# 04_MCU.net
KiCad netlist of a schematic drawn in Altium Designer
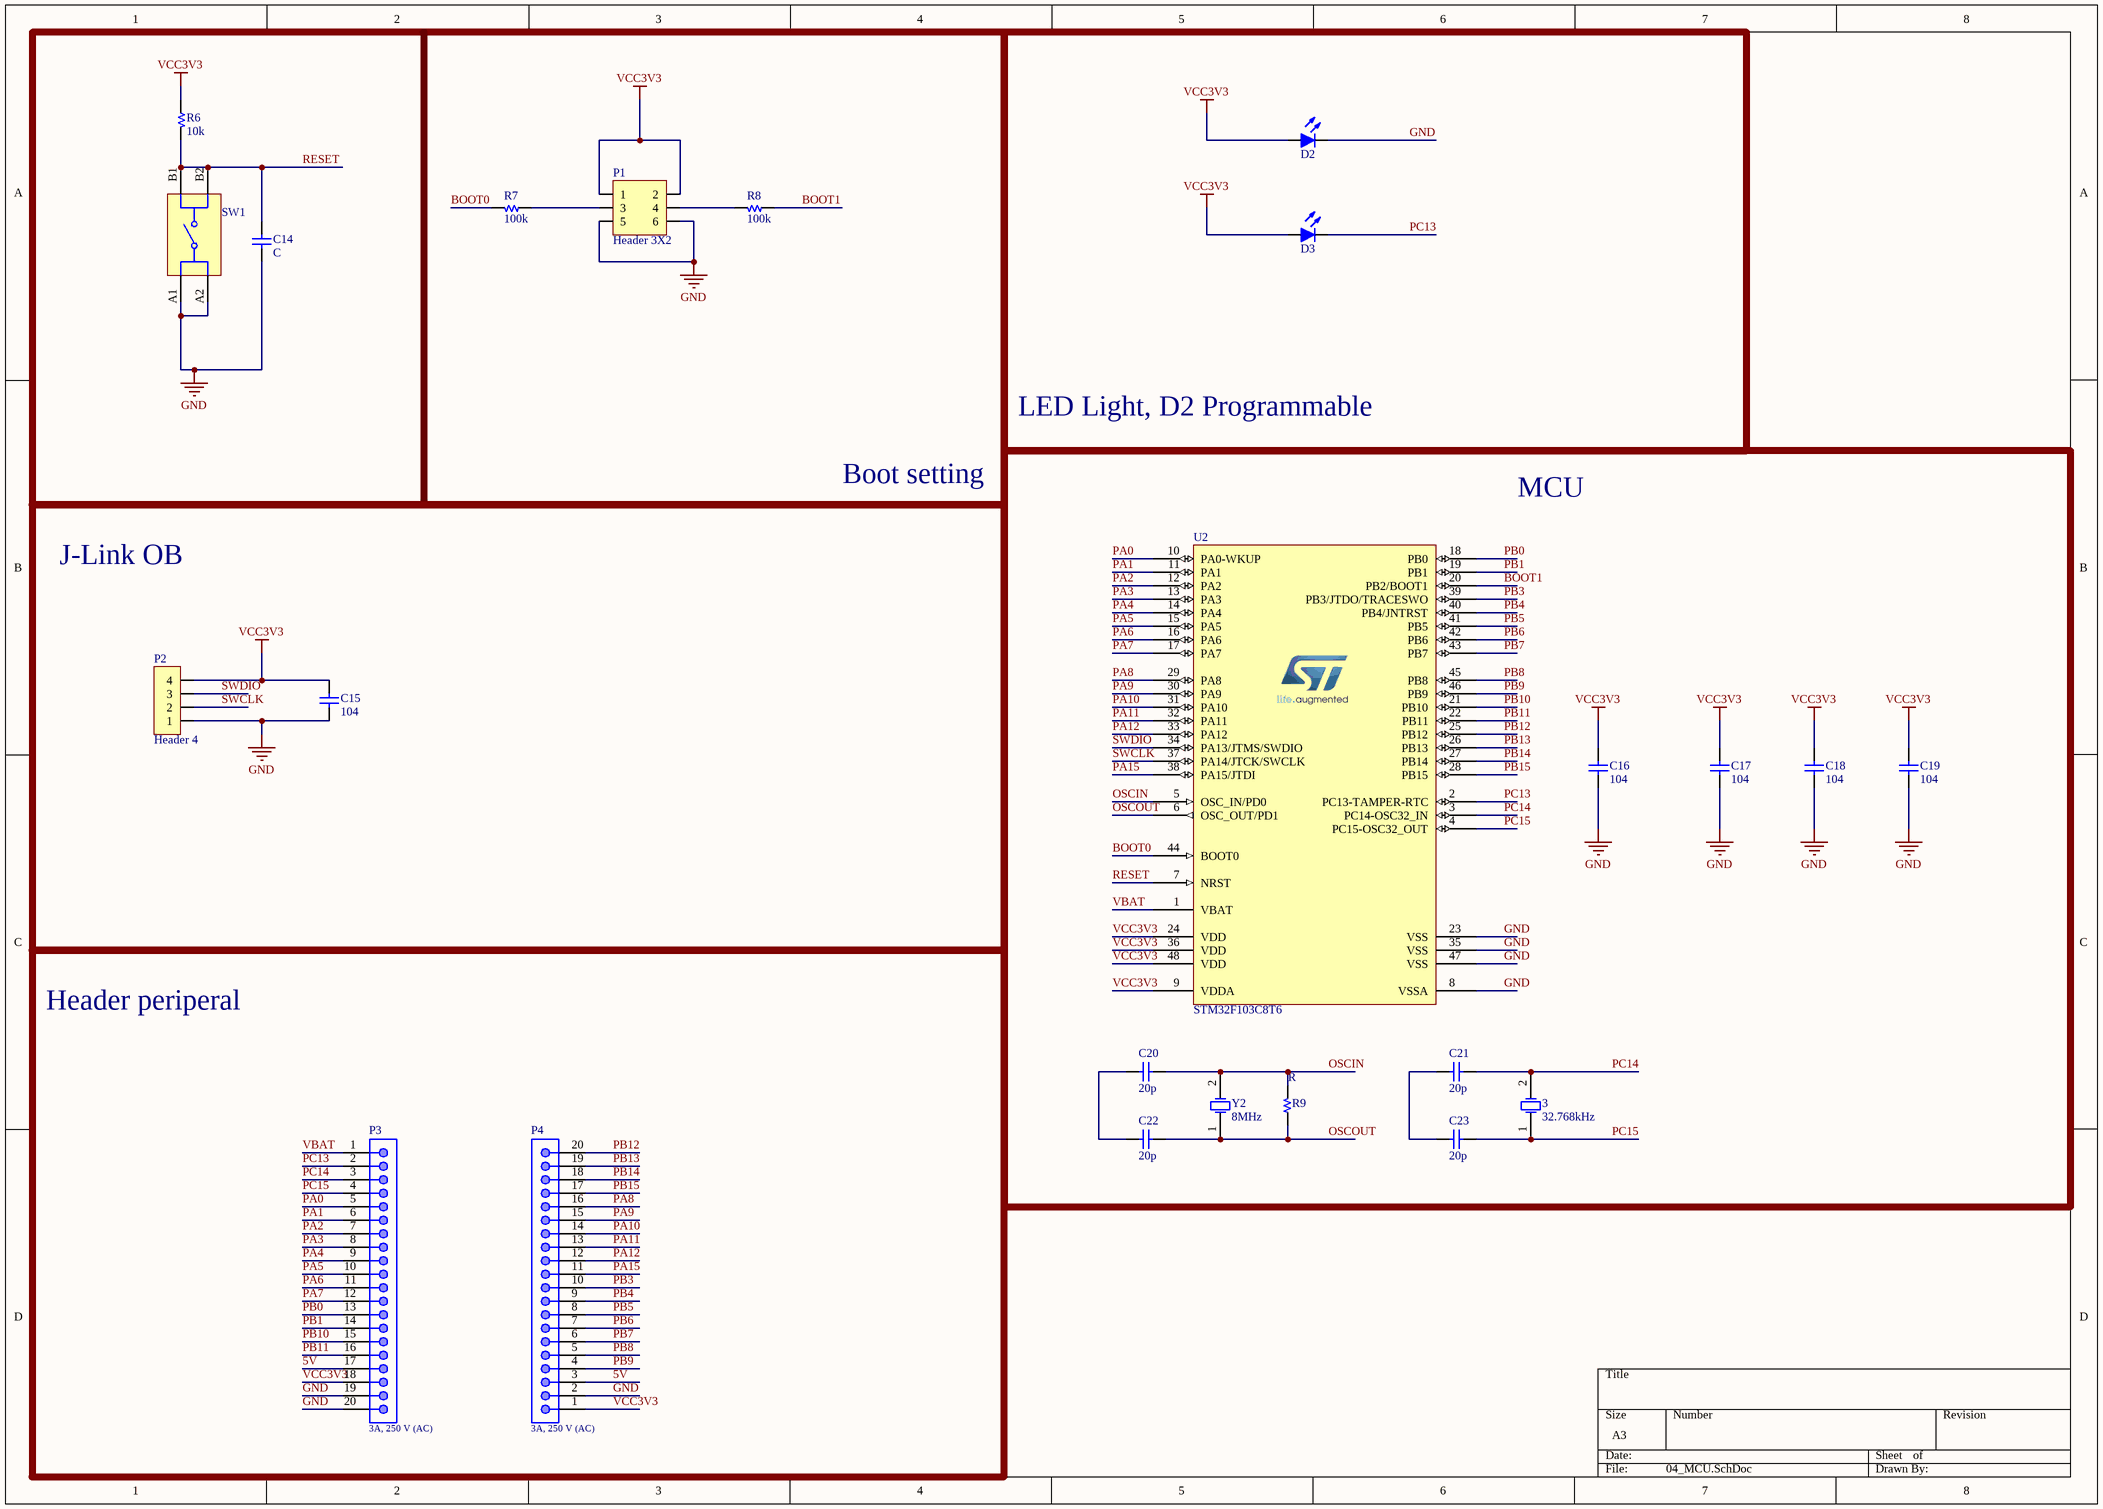
[diagram p0: 04_MCU.SchDoc]

(export (version "E")
  (design (tool "Eeschema 10.0.6"))
  (components
    (comp (ref "3")
      (value "32.768kHz")
      (footprint "XKXGI-SUA-32.768K")
      (description "32.768kHz Surface Mount Crystal 12.5pF ±20ppm ±30ppm SMD3215-2P Crystals ROHS")
      (fields (field (name "LCSC PART #") "C5213671") (field (name "MANUFACTURER") "YXC Crystal Oscillators"))
      (libsource (lib "Altium_XTAL_WATCH") (part "XKXGI-SUA-32.768K"))
    )
    (comp (ref "C14")
      (value "C")
      (footprint "C 0603")
      (description "Capacitor non-pol")
      (libsource (lib "chipfc_libs") (part "Capacitor NP"))
    )
    (comp (ref "C15")
      (value "104")
      (footprint "C 0805")
      (description "Capacitor non-pol")
      (libsource (lib "chipfc_libs") (part "Capacitor NP"))
    )
    (comp (ref "C16")
      (value "104")
      (footprint "C 0805")
      (description "Capacitor non-pol")
      (libsource (lib "chipfc_libs") (part "Capacitor NP"))
    )
    (comp (ref "C17")
      (value "104")
      (footprint "C 0805")
      (description "Capacitor non-pol")
      (libsource (lib "chipfc_libs") (part "Capacitor NP"))
    )
    (comp (ref "C18")
      (value "104")
      (footprint "C 0805")
      (description "Capacitor non-pol")
      (libsource (lib "chipfc_libs") (part "Capacitor NP"))
    )
    (comp (ref "C19")
      (value "104")
      (footprint "C 0805")
      (description "Capacitor non-pol")
      (libsource (lib "chipfc_libs") (part "Capacitor NP"))
    )
    (comp (ref "C20")
      (value "20p")
      (footprint "C 0805")
      (description "Capacitor non-pol")
      (libsource (lib "chipfc_libs") (part "Capacitor NP"))
    )
    (comp (ref "C21")
      (value "20p")
      (footprint "C 0805")
      (description "Capacitor non-pol")
      (libsource (lib "chipfc_libs") (part "Capacitor NP"))
    )
    (comp (ref "C22")
      (value "20p")
      (footprint "C 0805")
      (description "Capacitor non-pol")
      (libsource (lib "chipfc_libs") (part "Capacitor NP"))
    )
    (comp (ref "C23")
      (value "20p")
      (footprint "C 0805")
      (description "Capacitor non-pol")
      (libsource (lib "chipfc_libs") (part "Capacitor NP"))
    )
    (comp (ref "D2")
      (value "Led")
      (footprint "Led 0805")
      (description "Typical LED")
      (libsource (lib "led") (part "Led"))
    )
    (comp (ref "D3")
      (value "Led")
      (footprint "Led 0805")
      (description "Typical LED")
      (libsource (lib "led") (part "Led"))
    )
    (comp (ref "P1")
      (value "Header 3X2")
      (footprint "HDR/Header/6/DL")
      (description "Header, 3-Pin, Dual row")
      (libsource (lib "connectors") (part "Header 3X2"))
    )
    (comp (ref "P2")
      (value "Header 4")
      (footprint "HDR/Header/4")
      (description "Header, 4-Pin")
      (libsource (lib "connectors") (part "Header 4"))
    )
    (comp (ref "P3")
      (value "3A, 250 V (AC)")
      (footprint "61302011121")
      (description "WR-PHD Pin Header, THT, pitch 2.54mm, Single Row, Vertical, 20p")
      (fields
        (field (name "MANUFACTURER PART NUMBER") "61302011121")
        (field (name "MANUFACTURER") "Wurth Elektronik")
      )
      (libsource (lib "WR-PHD_Pin Header_2.54mm") (part "61302011121"))
    )
    (comp (ref "P4")
      (value "3A, 250 V (AC)")
      (footprint "61302011121")
      (description "WR-PHD Pin Header, THT, pitch 2.54mm, Single Row, Vertical, 20p")
      (fields
        (field (name "MANUFACTURER PART NUMBER") "61302011121")
        (field (name "MANUFACTURER") "Wurth Elektronik")
      )
      (libsource (lib "WR-PHD_Pin Header_2.54mm") (part "61302011121"))
    )
    (comp (ref "R6")
      (value "10k")
      (footprint "R 0805")
      (description "Resistor")
      (libsource (lib "chipfc_libs") (part "Resistor"))
    )
    (comp (ref "R7")
      (value "100k")
      (footprint "R 0805")
      (description "Resistor")
      (libsource (lib "chipfc_libs") (part "Resistor"))
    )
    (comp (ref "R8")
      (value "100k")
      (footprint "R 0805")
      (description "Resistor")
      (libsource (lib "chipfc_libs") (part "Resistor"))
    )
    (comp (ref "R9")
      (value "R")
      (footprint "R 0805")
      (description "Resistor")
      (libsource (lib "chipfc_libs") (part "Resistor"))
    )
    (comp (ref "SW1")
      (value "430152043826")
      (footprint "WS-TASV_L6W6H4.3_4301x20438x6")
      (description "WS-TASV SMT Tact Switch, L6 x W6 x H4.3mm, 260g, SPST-NO, 12V, 50mA")
      (fields (field (name "MANUFACTURER") "Wurth Elektronik"))
      (libsource (lib "Button") (part "430152043826"))
    )
    (comp (ref "U2")
      (value "STM32F103C8T6")
      (footprint "STM32F103C8T6")
      (description "ARM Microcontrollers - MCU 32BIT Cortex M3 64KB 20KB RAM 2X12 ADC")
      (fields
        (field (name "MANUFACTURER") "STMicroelectronics")
        (field (name "MANUFACTURER PART NUMBER") "STM32F103C8T6TR")
      )
      (libsource (lib "STM32") (part "STM32F103C8T6"))
    )
    (comp (ref "Y2")
      (value "8MHz")
      (footprint "WE-XTAL_HC49/4HSMX")
      (description "WE-XTAL Quartz Crystal, SMT, HC49/4HSMX, 8MHz, +/-30ppm")
      (fields
        (field (name "MANUFACTURER PART NUMBER") "830003151")
        (field (name "MANUFACTURER") "Wurth Elektronik")
      )
      (libsource (lib "Altium_XTAL_2PIN") (part "071105086016"))
    )
  )
  (nets
    (net (code "1") (name "/5V") (class "Default")
      (node (ref "P3") (pin "17") (pinfunction "17_17") (pintype "passive"))
      (node (ref "P4") (pin "3") (pinfunction "3_3") (pintype "passive"))
    )
    (net (code "2") (name "/BOOT0") (class "Default")
      (node (ref "R7") (pin "2") (pinfunction "2_2") (pintype "passive"))
      (node (ref "U2") (pin "44") (pinfunction "BOOT0_44") (pintype "input"))
    )
    (net (code "3") (name "/BOOT1") (class "Default")
      (node (ref "R8") (pin "1") (pinfunction "1_1") (pintype "passive"))
      (node (ref "U2") (pin "20") (pinfunction "PB2/BOOT1_20") (pintype "bidirectional"))
    )
    (net (code "4") (name "/OSCIN") (class "Default")
      (node (ref "C20") (pin "1") (pinfunction "1_1") (pintype "passive"))
      (node (ref "R9") (pin "2") (pinfunction "2_2") (pintype "passive"))
      (node (ref "U2") (pin "5") (pinfunction "OSC_IN/PD0_5") (pintype "input"))
      (node (ref "Y2") (pin "2") (pinfunction "OSC2_2") (pintype "passive"))
    )
    (net (code "5") (name "/OSCOUT") (class "Default")
      (node (ref "C22") (pin "1") (pinfunction "1_1") (pintype "passive"))
      (node (ref "R9") (pin "1") (pinfunction "1_1") (pintype "passive"))
      (node (ref "U2") (pin "6") (pinfunction "OSC_OUT/PD1_6") (pintype "output"))
      (node (ref "Y2") (pin "1") (pinfunction "OSC1_1") (pintype "passive"))
    )
    (net (code "6") (name "/PA0") (class "Default")
      (node (ref "P3") (pin "5") (pinfunction "5_5") (pintype "passive"))
      (node (ref "U2") (pin "10") (pinfunction "PA0-WKUP_10") (pintype "bidirectional"))
    )
    (net (code "7") (name "/PA1") (class "Default")
      (node (ref "P3") (pin "6") (pinfunction "6_6") (pintype "passive"))
      (node (ref "U2") (pin "11") (pinfunction "PA1_11") (pintype "bidirectional"))
    )
    (net (code "8") (name "/PA2") (class "Default")
      (node (ref "P3") (pin "7") (pinfunction "7_7") (pintype "passive"))
      (node (ref "U2") (pin "12") (pinfunction "PA2_12") (pintype "bidirectional"))
    )
    (net (code "9") (name "/PA3") (class "Default")
      (node (ref "P3") (pin "8") (pinfunction "8_8") (pintype "passive"))
      (node (ref "U2") (pin "13") (pinfunction "PA3_13") (pintype "bidirectional"))
    )
    (net (code "10") (name "/PA4") (class "Default")
      (node (ref "P3") (pin "9") (pinfunction "9_9") (pintype "passive"))
      (node (ref "U2") (pin "14") (pinfunction "PA4_14") (pintype "bidirectional"))
    )
    (net (code "11") (name "/PA5") (class "Default")
      (node (ref "P3") (pin "10") (pinfunction "10_10") (pintype "passive"))
      (node (ref "U2") (pin "15") (pinfunction "PA5_15") (pintype "bidirectional"))
    )
    (net (code "12") (name "/PA6") (class "Default")
      (node (ref "P3") (pin "11") (pinfunction "11_11") (pintype "passive"))
      (node (ref "U2") (pin "16") (pinfunction "PA6_16") (pintype "bidirectional"))
    )
    (net (code "13") (name "/PA7") (class "Default")
      (node (ref "P3") (pin "12") (pinfunction "12_12") (pintype "passive"))
      (node (ref "U2") (pin "17") (pinfunction "PA7_17") (pintype "bidirectional"))
    )
    (net (code "14") (name "/PA8") (class "Default")
      (node (ref "P4") (pin "16") (pinfunction "16_16") (pintype "passive"))
      (node (ref "U2") (pin "29") (pinfunction "PA8_29") (pintype "bidirectional"))
    )
    (net (code "15") (name "/PA9") (class "Default")
      (node (ref "P4") (pin "15") (pinfunction "15_15") (pintype "passive"))
      (node (ref "U2") (pin "30") (pinfunction "PA9_30") (pintype "bidirectional"))
    )
    (net (code "16") (name "/PA10") (class "Default")
      (node (ref "P4") (pin "14") (pinfunction "14_14") (pintype "passive"))
      (node (ref "U2") (pin "31") (pinfunction "PA10_31") (pintype "bidirectional"))
    )
    (net (code "17") (name "/PA11") (class "Default")
      (node (ref "P4") (pin "13") (pinfunction "13_13") (pintype "passive"))
      (node (ref "U2") (pin "32") (pinfunction "PA11_32") (pintype "bidirectional"))
    )
    (net (code "18") (name "/PA12") (class "Default")
      (node (ref "P4") (pin "12") (pinfunction "12_12") (pintype "passive"))
      (node (ref "U2") (pin "33") (pinfunction "PA12_33") (pintype "bidirectional"))
    )
    (net (code "19") (name "/PA15") (class "Default")
      (node (ref "P4") (pin "11") (pinfunction "11_11") (pintype "passive"))
      (node (ref "U2") (pin "38") (pinfunction "PA15/JTDI_38") (pintype "bidirectional"))
    )
    (net (code "20") (name "/PB0") (class "Default")
      (node (ref "P3") (pin "13") (pinfunction "13_13") (pintype "passive"))
      (node (ref "U2") (pin "18") (pinfunction "PB0_18") (pintype "bidirectional"))
    )
    (net (code "21") (name "/PB1") (class "Default")
      (node (ref "P3") (pin "14") (pinfunction "14_14") (pintype "passive"))
      (node (ref "U2") (pin "19") (pinfunction "PB1_19") (pintype "bidirectional"))
    )
    (net (code "22") (name "/PB3") (class "Default")
      (node (ref "P4") (pin "10") (pinfunction "10_10") (pintype "passive"))
      (node (ref "U2") (pin "39") (pinfunction "PB3/JTDO/TRACESWO_39") (pintype "bidirectional"))
    )
    (net (code "23") (name "/PB4") (class "Default")
      (node (ref "P4") (pin "9") (pinfunction "9_9") (pintype "passive"))
      (node (ref "U2") (pin "40") (pinfunction "PB4/JNTRST_40") (pintype "bidirectional"))
    )
    (net (code "24") (name "/PB5") (class "Default")
      (node (ref "P4") (pin "8") (pinfunction "8_8") (pintype "passive"))
      (node (ref "U2") (pin "41") (pinfunction "PB5_41") (pintype "bidirectional"))
    )
    (net (code "25") (name "/PB6") (class "Default")
      (node (ref "P4") (pin "7") (pinfunction "7_7") (pintype "passive"))
      (node (ref "U2") (pin "42") (pinfunction "PB6_42") (pintype "bidirectional"))
    )
    (net (code "26") (name "/PB7") (class "Default")
      (node (ref "P4") (pin "6") (pinfunction "6_6") (pintype "passive"))
      (node (ref "U2") (pin "43") (pinfunction "PB7_43") (pintype "bidirectional"))
    )
    (net (code "27") (name "/PB8") (class "Default")
      (node (ref "P4") (pin "5") (pinfunction "5_5") (pintype "passive"))
      (node (ref "U2") (pin "45") (pinfunction "PB8_45") (pintype "bidirectional"))
    )
    (net (code "28") (name "/PB9") (class "Default")
      (node (ref "P4") (pin "4") (pinfunction "4_4") (pintype "passive"))
      (node (ref "U2") (pin "46") (pinfunction "PB9_46") (pintype "bidirectional"))
    )
    (net (code "29") (name "/PB10") (class "Default")
      (node (ref "P3") (pin "15") (pinfunction "15_15") (pintype "passive"))
      (node (ref "U2") (pin "21") (pinfunction "PB10_21") (pintype "bidirectional"))
    )
    (net (code "30") (name "/PB11") (class "Default")
      (node (ref "P3") (pin "16") (pinfunction "16_16") (pintype "passive"))
      (node (ref "U2") (pin "22") (pinfunction "PB11_22") (pintype "bidirectional"))
    )
    (net (code "31") (name "/PB12") (class "Default")
      (node (ref "P4") (pin "20") (pinfunction "20_20") (pintype "passive"))
      (node (ref "U2") (pin "25") (pinfunction "PB12_25") (pintype "bidirectional"))
    )
    (net (code "32") (name "/PB13") (class "Default")
      (node (ref "P4") (pin "19") (pinfunction "19_19") (pintype "passive"))
      (node (ref "U2") (pin "26") (pinfunction "PB13_26") (pintype "bidirectional"))
    )
    (net (code "33") (name "/PB14") (class "Default")
      (node (ref "P4") (pin "18") (pinfunction "18_18") (pintype "passive"))
      (node (ref "U2") (pin "27") (pinfunction "PB14_27") (pintype "bidirectional"))
    )
    (net (code "34") (name "/PB15") (class "Default")
      (node (ref "P4") (pin "17") (pinfunction "17_17") (pintype "passive"))
      (node (ref "U2") (pin "28") (pinfunction "PB15_28") (pintype "bidirectional"))
    )
    (net (code "35") (name "/PC13") (class "Default")
      (node (ref "D3") (pin "2") (pinfunction "K_2") (pintype "passive"))
      (node (ref "P3") (pin "2") (pinfunction "2_2") (pintype "passive"))
      (node (ref "U2") (pin "2") (pinfunction "PC13-TAMPER-RTC_2") (pintype "bidirectional"))
    )
    (net (code "36") (name "/PC14") (class "Default")
      (node (ref "3") (pin "2") (pinfunction "OSC2_2") (pintype "passive"))
      (node (ref "C21") (pin "1") (pinfunction "1_1") (pintype "passive"))
      (node (ref "P3") (pin "3") (pinfunction "3_3") (pintype "passive"))
      (node (ref "U2") (pin "3") (pinfunction "PC14-OSC32_IN_3") (pintype "bidirectional"))
    )
    (net (code "37") (name "/PC15") (class "Default")
      (node (ref "3") (pin "1") (pinfunction "OSC1_1") (pintype "passive"))
      (node (ref "C23") (pin "1") (pinfunction "1_1") (pintype "passive"))
      (node (ref "P3") (pin "4") (pinfunction "4_4") (pintype "passive"))
      (node (ref "U2") (pin "4") (pinfunction "PC15-OSC32_OUT_4") (pintype "bidirectional"))
    )
    (net (code "38") (name "/RESET") (class "Default")
      (node (ref "C14") (pin "1") (pinfunction "1_1") (pintype "passive"))
      (node (ref "R6") (pin "2") (pinfunction "2_2") (pintype "passive"))
      (node (ref "SW1") (pin "B1") (pinfunction "B1_B1") (pintype "passive"))
      (node (ref "SW1") (pin "B2") (pinfunction "B2_B2") (pintype "passive"))
      (node (ref "U2") (pin "7") (pinfunction "NRST_7") (pintype "input"))
    )
    (net (code "39") (name "/SWCLK") (class "Default")
      (node (ref "P2") (pin "2") (pinfunction "2_2") (pintype "passive"))
      (node (ref "U2") (pin "37") (pinfunction "PA14/JTCK/SWCLK_37") (pintype "bidirectional"))
    )
    (net (code "40") (name "/SWDIO") (class "Default")
      (node (ref "P2") (pin "3") (pinfunction "3_3") (pintype "passive"))
      (node (ref "U2") (pin "34") (pinfunction "PA13/JTMS/SWDIO_34") (pintype "bidirectional"))
    )
    (net (code "41") (name "/VBAT") (class "Default")
      (node (ref "P3") (pin "1") (pinfunction "1_1") (pintype "passive"))
      (node (ref "U2") (pin "1") (pinfunction "VBAT_1") (pintype "power_in"))
    )
    (net (code "42") (name "GND") (class "Default")
      (node (ref "C14") (pin "2") (pinfunction "2_2") (pintype "passive"))
      (node (ref "C15") (pin "2") (pinfunction "2_2") (pintype "passive"))
      (node (ref "C16") (pin "1") (pinfunction "1_1") (pintype "passive"))
      (node (ref "C17") (pin "1") (pinfunction "1_1") (pintype "passive"))
      (node (ref "C18") (pin "1") (pinfunction "1_1") (pintype "passive"))
      (node (ref "C19") (pin "1") (pinfunction "1_1") (pintype "passive"))
      (node (ref "D2") (pin "2") (pinfunction "K_2") (pintype "passive"))
      (node (ref "P1") (pin "5") (pinfunction "5_5") (pintype "passive"))
      (node (ref "P1") (pin "6") (pinfunction "6_6") (pintype "passive"))
      (node (ref "P2") (pin "1") (pinfunction "1_1") (pintype "passive"))
      (node (ref "P3") (pin "19") (pinfunction "19_19") (pintype "passive"))
      (node (ref "P3") (pin "20") (pinfunction "20_20") (pintype "passive"))
      (node (ref "P4") (pin "2") (pinfunction "2_2") (pintype "passive"))
      (node (ref "SW1") (pin "A1") (pinfunction "A1_A1") (pintype "passive"))
      (node (ref "SW1") (pin "A2") (pinfunction "A2_A2") (pintype "passive"))
      (node (ref "U2") (pin "23") (pinfunction "VSS_23") (pintype "power_in"))
      (node (ref "U2") (pin "35") (pinfunction "VSS_35") (pintype "power_in"))
      (node (ref "U2") (pin "47") (pinfunction "VSS_47") (pintype "power_in"))
      (node (ref "U2") (pin "8") (pinfunction "VSSA_8") (pintype "power_in"))
    )
    (net (code "43") (name "Net-(C20-Pad2)") (class "Default")
      (node (ref "C20") (pin "2") (pinfunction "2_2") (pintype "passive"))
      (node (ref "C22") (pin "2") (pinfunction "2_2") (pintype "passive"))
    )
    (net (code "44") (name "Net-(C21-Pad2)") (class "Default")
      (node (ref "C21") (pin "2") (pinfunction "2_2") (pintype "passive"))
      (node (ref "C23") (pin "2") (pinfunction "2_2") (pintype "passive"))
    )
    (net (code "45") (name "Net-(P1-Pad3)") (class "Default")
      (node (ref "P1") (pin "3") (pinfunction "3_3") (pintype "passive"))
      (node (ref "R7") (pin "1") (pinfunction "1_1") (pintype "passive"))
    )
    (net (code "46") (name "Net-(P1-Pad4)") (class "Default")
      (node (ref "P1") (pin "4") (pinfunction "4_4") (pintype "passive"))
      (node (ref "R8") (pin "2") (pinfunction "2_2") (pintype "passive"))
    )
    (net (code "47") (name "VCC3V3") (class "Default")
      (node (ref "C15") (pin "1") (pinfunction "1_1") (pintype "passive"))
      (node (ref "C16") (pin "2") (pinfunction "2_2") (pintype "passive"))
      (node (ref "C17") (pin "2") (pinfunction "2_2") (pintype "passive"))
      (node (ref "C18") (pin "2") (pinfunction "2_2") (pintype "passive"))
      (node (ref "C19") (pin "2") (pinfunction "2_2") (pintype "passive"))
      (node (ref "D2") (pin "1") (pinfunction "A_1") (pintype "passive"))
      (node (ref "D3") (pin "1") (pinfunction "A_1") (pintype "passive"))
      (node (ref "P1") (pin "1") (pinfunction "1_1") (pintype "passive"))
      (node (ref "P1") (pin "2") (pinfunction "2_2") (pintype "passive"))
      (node (ref "P2") (pin "4") (pinfunction "4_4") (pintype "passive"))
      (node (ref "P3") (pin "18") (pinfunction "18_18") (pintype "passive"))
      (node (ref "P4") (pin "1") (pinfunction "1_1") (pintype "passive"))
      (node (ref "R6") (pin "1") (pinfunction "1_1") (pintype "passive"))
      (node (ref "U2") (pin "24") (pinfunction "VDD_24") (pintype "power_in"))
      (node (ref "U2") (pin "36") (pinfunction "VDD_36") (pintype "power_in"))
      (node (ref "U2") (pin "48") (pinfunction "VDD_48") (pintype "power_in"))
      (node (ref "U2") (pin "9") (pinfunction "VDDA_9") (pintype "power_in"))
    )
  )
)
